# Keg_Cop_-_New_8-Pack.net
KiCad netlist of a schematic drawn in EAGLE
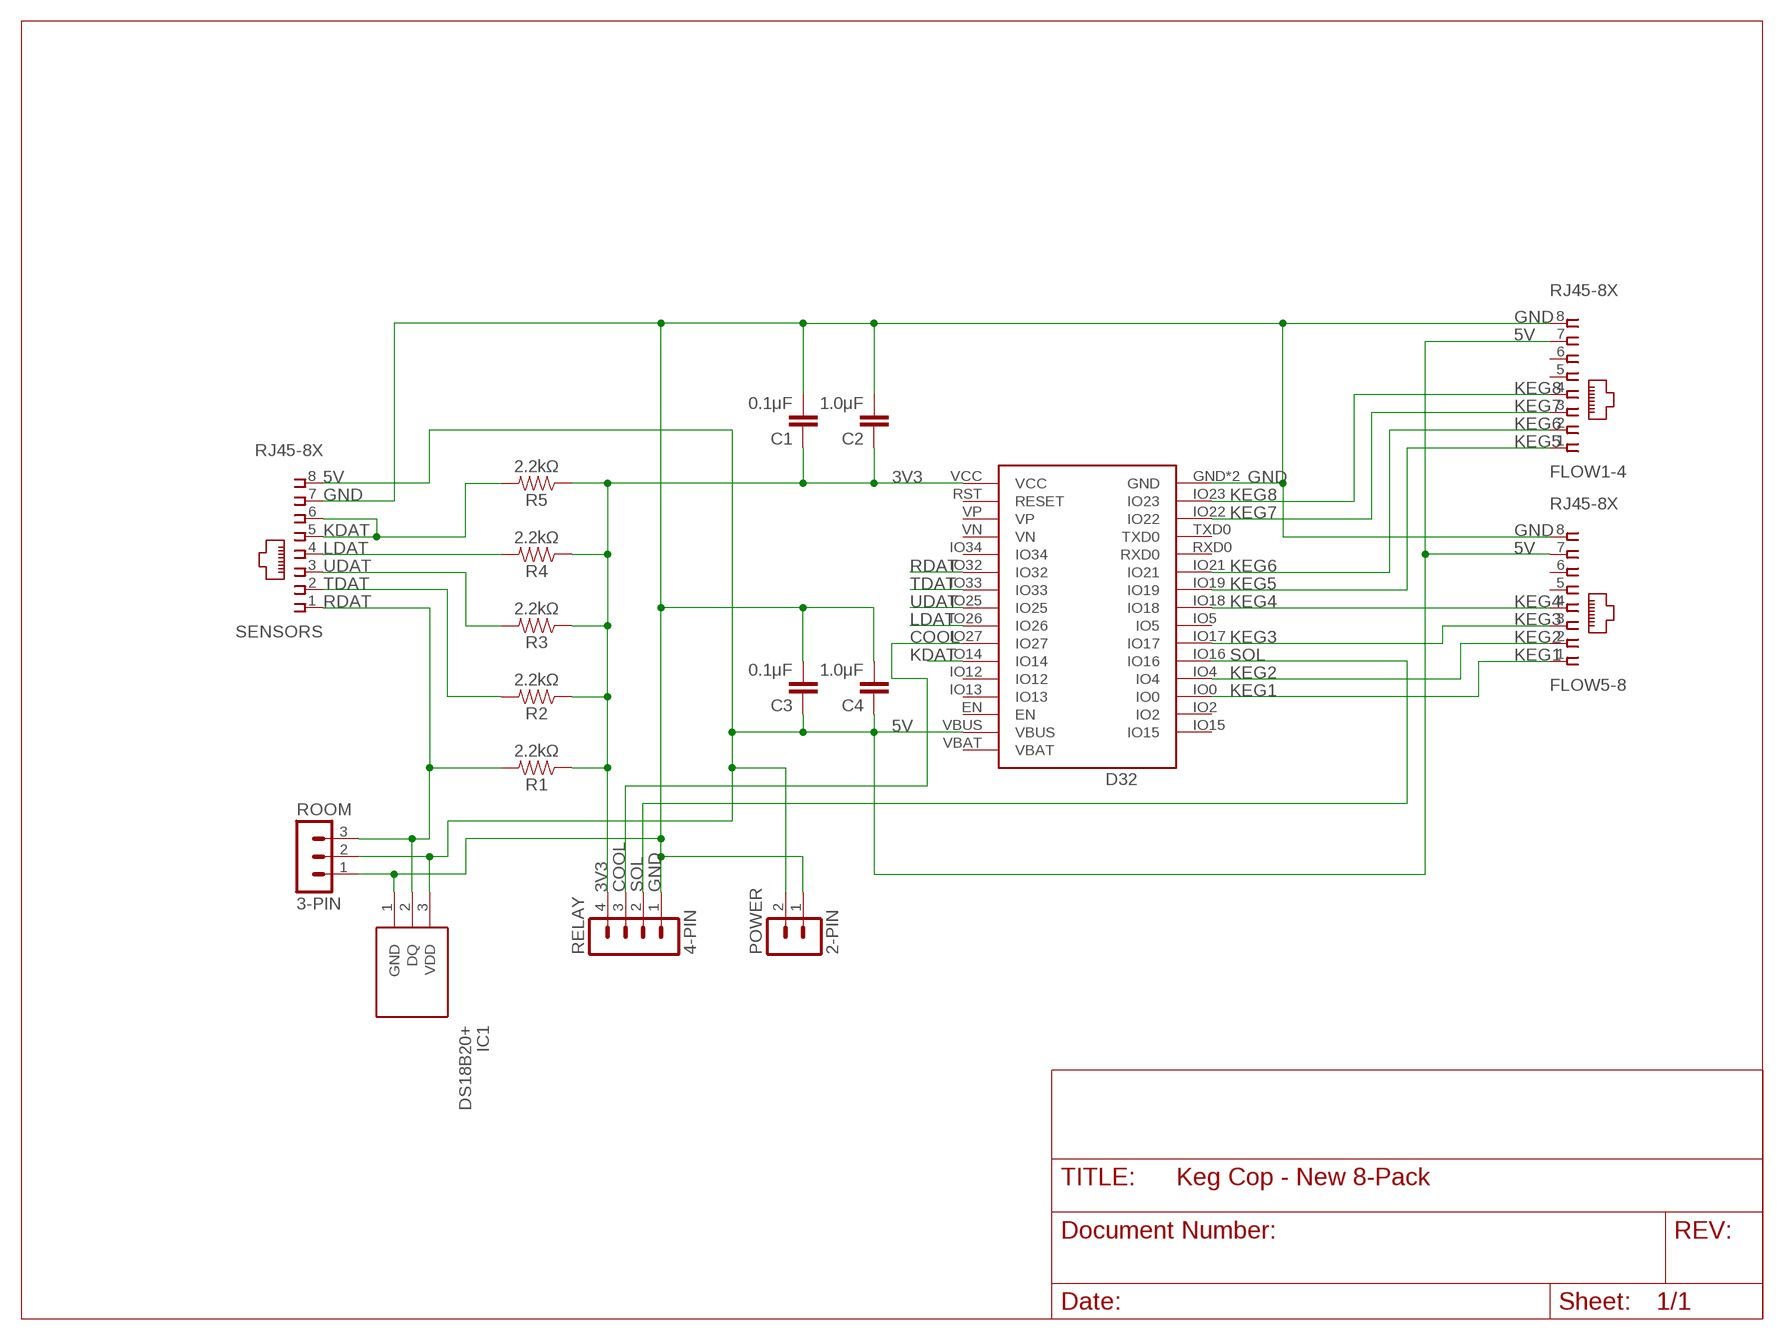
[diagram p0: schematic, sheet 1]

(export (version "E")
  (design (tool "Eeschema 10.0.6"))
  (components
    (comp (ref "C1")
      (value "0.1μF")
      (footprint "eagle-import:CAP_PTH-2.54")
      (libsource (lib "eagle-import") (part "CAP_CERAMIC_2.54"))
    )
    (comp (ref "C2")
      (value "1.0μF")
      (footprint "eagle-import:CAP_PTH-2.54")
      (libsource (lib "eagle-import") (part "CAP_CERAMIC_2.54"))
    )
    (comp (ref "C3")
      (value "0.1μF")
      (footprint "eagle-import:CAP_PTH-2.54")
      (libsource (lib "eagle-import") (part "CAP_CERAMIC_2.54"))
    )
    (comp (ref "C4")
      (value "1.0μF")
      (footprint "eagle-import:CAP_PTH-2.54")
      (libsource (lib "eagle-import") (part "CAP_CERAMIC_2.54"))
    )
    (comp (ref "D32")
      (value "Lolin D32")
      (footprint "eagle-import:D32_NO_BATT")
      (libsource (lib "eagle-import") (part "WEMOS-D32D32_NO_BATT"))
    )
    (comp (ref "FLOW1-4")
      (value "RJ45-8X")
      (footprint "eagle-import:RJ45-NO-SHIELD")
      (libsource (lib "eagle-import") (part "RJ45-8X"))
    )
    (comp (ref "FLOW5-8")
      (value "RJ45-8X")
      (footprint "eagle-import:RJ45-NO-SHIELD")
      (libsource (lib "eagle-import") (part "RJ45-8X"))
    )
    (comp (ref "IC1")
      (value "DS18B20+")
      (footprint "eagle-import:TO-92")
      (fields (field (name "MOUSER_PART_NUMBER") "700-DS18B20+"))
      (libsource (lib "eagle-import") (part "DS18B20+"))
    )
    (comp (ref "POWER")
      (value "2-PIN")
      (footprint "eagle-import:HDR-2_VERT")
      (libsource (lib "eagle-import") (part "HDR-2"))
    )
    (comp (ref "R1")
      (value "2.2kΩ")
      (footprint "eagle-import:AXIAL-0.3")
      (libsource (lib "eagle-import") (part "RESISTORAXIAL-0.3"))
    )
    (comp (ref "R2")
      (value "2.2kΩ")
      (footprint "eagle-import:AXIAL-0.3")
      (libsource (lib "eagle-import") (part "RESISTORAXIAL-0.3"))
    )
    (comp (ref "R3")
      (value "2.2kΩ")
      (footprint "eagle-import:AXIAL-0.3")
      (libsource (lib "eagle-import") (part "RESISTORAXIAL-0.3"))
    )
    (comp (ref "R4")
      (value "2.2kΩ")
      (footprint "eagle-import:AXIAL-0.3")
      (libsource (lib "eagle-import") (part "RESISTORAXIAL-0.3"))
    )
    (comp (ref "R5")
      (value "2.2kΩ")
      (footprint "eagle-import:AXIAL-0.3")
      (libsource (lib "eagle-import") (part "RESISTORAXIAL-0.3"))
    )
    (comp (ref "RELAY")
      (value "4-PIN")
      (footprint "eagle-import:MA04-1")
      (libsource (lib "eagle-import") (part "MA04-1"))
    )
    (comp (ref "ROOM")
      (value "3-PIN")
      (footprint "eagle-import:HDR-3_VERT")
      (libsource (lib "eagle-import") (part "HDR-3"))
    )
    (comp (ref "SENSORS")
      (value "RJ45-8X")
      (footprint "eagle-import:RJ45-NO-SHIELD")
      (libsource (lib "eagle-import") (part "RJ45-8X"))
    )
  )
  (nets
    (net (code "1") (name "/3V3") (class "Default")
      (node (ref "C1") (pin "1") (pinfunction "1_1") (pintype "passive"))
      (node (ref "C2") (pin "1") (pinfunction "1_1") (pintype "passive"))
      (node (ref "D32") (pin "VCC") (pinfunction "VCC_VCC") (pintype "power_in"))
      (node (ref "R1") (pin "P$1") (pinfunction "1_P$1") (pintype "passive"))
      (node (ref "R2") (pin "P$1") (pinfunction "1_P$1") (pintype "passive"))
      (node (ref "R3") (pin "P$1") (pinfunction "1_P$1") (pintype "passive"))
      (node (ref "R4") (pin "P$1") (pinfunction "1_P$1") (pintype "passive"))
      (node (ref "R5") (pin "P$1") (pinfunction "1_P$1") (pintype "passive"))
      (node (ref "RELAY") (pin "4") (pinfunction "4_4") (pintype "passive"))
    )
    (net (code "2") (name "/5V") (class "Default")
      (node (ref "C3") (pin "1") (pinfunction "1_1") (pintype "passive"))
      (node (ref "C4") (pin "1") (pinfunction "1_1") (pintype "passive"))
      (node (ref "D32") (pin "VBUS") (pinfunction "VBUS_VBUS") (pintype "bidirectional"))
      (node (ref "FLOW1-4") (pin "7") (pinfunction "7_7") (pintype "passive"))
      (node (ref "FLOW5-8") (pin "7") (pinfunction "7_7") (pintype "passive"))
      (node (ref "IC1") (pin "3") (pinfunction "VDD_3") (pintype "power_in"))
      (node (ref "POWER") (pin "2") (pinfunction "2_2") (pintype "passive"))
      (node (ref "ROOM") (pin "2") (pinfunction "2_2") (pintype "passive"))
      (node (ref "SENSORS") (pin "8") (pinfunction "8_8") (pintype "passive"))
    )
    (net (code "3") (name "/COOL") (class "Default")
      (node (ref "D32") (pin "IO27") (pinfunction "IO27_IO27") (pintype "bidirectional"))
      (node (ref "RELAY") (pin "3") (pinfunction "3_3") (pintype "passive"))
    )
    (net (code "4") (name "/GND") (class "Default")
      (node (ref "C1") (pin "2") (pinfunction "2_2") (pintype "passive"))
      (node (ref "C2") (pin "2") (pinfunction "2_2") (pintype "passive"))
      (node (ref "C3") (pin "2") (pinfunction "2_2") (pintype "passive"))
      (node (ref "C4") (pin "2") (pinfunction "2_2") (pintype "passive"))
      (node (ref "D32") (pin "GND") (pinfunction "GND_GND") (pintype "power_in"))
      (node (ref "D32") (pin "GND2") (pinfunction "GND_GND2") (pintype "power_in"))
      (node (ref "FLOW1-4") (pin "8") (pinfunction "8_8") (pintype "passive"))
      (node (ref "FLOW5-8") (pin "8") (pinfunction "8_8") (pintype "passive"))
      (node (ref "IC1") (pin "1") (pinfunction "GND_1") (pintype "power_in"))
      (node (ref "POWER") (pin "1") (pinfunction "1_1") (pintype "passive"))
      (node (ref "RELAY") (pin "1") (pinfunction "1_1") (pintype "passive"))
      (node (ref "ROOM") (pin "1") (pinfunction "1_1") (pintype "passive"))
      (node (ref "SENSORS") (pin "7") (pinfunction "7_7") (pintype "passive"))
    )
    (net (code "5") (name "/KDAT") (class "Default")
      (node (ref "D32") (pin "IO14") (pinfunction "IO14_IO14") (pintype "bidirectional"))
      (node (ref "R5") (pin "P$2") (pinfunction "2_P$2") (pintype "passive"))
      (node (ref "SENSORS") (pin "5") (pinfunction "5_5") (pintype "passive"))
      (node (ref "SENSORS") (pin "6") (pinfunction "6_6") (pintype "passive"))
    )
    (net (code "6") (name "/KEG1") (class "Default")
      (node (ref "D32") (pin "IO0") (pinfunction "IO0_IO0") (pintype "bidirectional"))
      (node (ref "FLOW5-8") (pin "1") (pinfunction "1_1") (pintype "passive"))
    )
    (net (code "7") (name "/KEG2") (class "Default")
      (node (ref "D32") (pin "IO4") (pinfunction "IO4_IO4") (pintype "bidirectional"))
      (node (ref "FLOW5-8") (pin "2") (pinfunction "2_2") (pintype "passive"))
    )
    (net (code "8") (name "/KEG3") (class "Default")
      (node (ref "D32") (pin "IO17") (pinfunction "IO17_IO17") (pintype "bidirectional"))
      (node (ref "FLOW5-8") (pin "3") (pinfunction "3_3") (pintype "passive"))
    )
    (net (code "9") (name "/KEG4") (class "Default")
      (node (ref "D32") (pin "IO18") (pinfunction "IO18_IO18") (pintype "bidirectional"))
      (node (ref "FLOW5-8") (pin "4") (pinfunction "4_4") (pintype "passive"))
    )
    (net (code "10") (name "/KEG5") (class "Default")
      (node (ref "D32") (pin "IO19") (pinfunction "IO19_IO19") (pintype "bidirectional"))
      (node (ref "FLOW1-4") (pin "1") (pinfunction "1_1") (pintype "passive"))
    )
    (net (code "11") (name "/KEG6") (class "Default")
      (node (ref "D32") (pin "IO21") (pinfunction "IO21_IO21") (pintype "bidirectional"))
      (node (ref "FLOW1-4") (pin "2") (pinfunction "2_2") (pintype "passive"))
    )
    (net (code "12") (name "/KEG7") (class "Default")
      (node (ref "D32") (pin "IO22") (pinfunction "IO22_IO22") (pintype "bidirectional"))
      (node (ref "FLOW1-4") (pin "3") (pinfunction "3_3") (pintype "passive"))
    )
    (net (code "13") (name "/KEG8") (class "Default")
      (node (ref "D32") (pin "IO23") (pinfunction "IO23_IO23") (pintype "bidirectional"))
      (node (ref "FLOW1-4") (pin "4") (pinfunction "4_4") (pintype "passive"))
    )
    (net (code "14") (name "/LDAT") (class "Default")
      (node (ref "D32") (pin "IO26") (pinfunction "IO26_IO26") (pintype "bidirectional"))
      (node (ref "R4") (pin "P$2") (pinfunction "2_P$2") (pintype "passive"))
      (node (ref "SENSORS") (pin "4") (pinfunction "4_4") (pintype "passive"))
    )
    (net (code "15") (name "/RDAT") (class "Default")
      (node (ref "D32") (pin "IO32") (pinfunction "IO32_IO32") (pintype "bidirectional"))
      (node (ref "IC1") (pin "2") (pinfunction "DQ_2") (pintype "bidirectional"))
      (node (ref "R1") (pin "P$2") (pinfunction "2_P$2") (pintype "passive"))
      (node (ref "ROOM") (pin "3") (pinfunction "3_3") (pintype "passive"))
      (node (ref "SENSORS") (pin "1") (pinfunction "1_1") (pintype "passive"))
    )
    (net (code "16") (name "/SOL") (class "Default")
      (node (ref "D32") (pin "IO16") (pinfunction "IO16_IO16") (pintype "bidirectional"))
      (node (ref "RELAY") (pin "2") (pinfunction "2_2") (pintype "passive"))
    )
    (net (code "17") (name "/TDAT") (class "Default")
      (node (ref "D32") (pin "IO33") (pinfunction "IO33_IO33") (pintype "bidirectional"))
      (node (ref "R2") (pin "P$2") (pinfunction "2_P$2") (pintype "passive"))
      (node (ref "SENSORS") (pin "2") (pinfunction "2_2") (pintype "passive"))
    )
    (net (code "18") (name "/UDAT") (class "Default")
      (node (ref "D32") (pin "IO25") (pinfunction "IO25_IO25") (pintype "bidirectional"))
      (node (ref "R3") (pin "P$2") (pinfunction "2_P$2") (pintype "passive"))
      (node (ref "SENSORS") (pin "3") (pinfunction "3_3") (pintype "passive"))
    )
    (net (code "19") (name "unconnected-(D32-PadEN)") (class "Default")
      (node (ref "D32") (pin "EN") (pinfunction "EN_EN") (pintype "bidirectional"))
    )
    (net (code "20") (name "unconnected-(D32-PadIO2)") (class "Default")
      (node (ref "D32") (pin "IO2") (pinfunction "IO2_IO2") (pintype "bidirectional"))
    )
    (net (code "21") (name "unconnected-(D32-PadIO5)") (class "Default")
      (node (ref "D32") (pin "IO5") (pinfunction "IO5_IO5") (pintype "bidirectional"))
    )
    (net (code "22") (name "unconnected-(D32-PadIO12)") (class "Default")
      (node (ref "D32") (pin "IO12") (pinfunction "IO12_IO12") (pintype "bidirectional"))
    )
    (net (code "23") (name "unconnected-(D32-PadIO13)") (class "Default")
      (node (ref "D32") (pin "IO13") (pinfunction "IO13_IO13") (pintype "bidirectional"))
    )
    (net (code "24") (name "unconnected-(D32-PadIO15)") (class "Default")
      (node (ref "D32") (pin "IO15") (pinfunction "IO15_IO15") (pintype "bidirectional"))
    )
    (net (code "25") (name "unconnected-(D32-PadIO34)") (class "Default")
      (node (ref "D32") (pin "IO34") (pinfunction "IO34_IO34") (pintype "bidirectional"))
    )
    (net (code "26") (name "unconnected-(D32-PadRXD0)") (class "Default")
      (node (ref "D32") (pin "RXD0") (pinfunction "RXD0_RXD0") (pintype "input"))
    )
    (net (code "27") (name "unconnected-(D32-PadTXD0)") (class "Default")
      (node (ref "D32") (pin "TXD0") (pinfunction "TXD0_TXD0") (pintype "output"))
    )
    (net (code "28") (name "unconnected-(D32-PadVBAT)") (class "Default")
      (node (ref "D32") (pin "VBAT") (pinfunction "VBAT_VBAT") (pintype "bidirectional"))
    )
    (net (code "29") (name "unconnected-(D32-PadVN)") (class "Default")
      (node (ref "D32") (pin "VN") (pinfunction "VN_VN") (pintype "bidirectional"))
    )
    (net (code "30") (name "unconnected-(D32-PadVP)") (class "Default")
      (node (ref "D32") (pin "VP") (pinfunction "VP_VP") (pintype "bidirectional"))
    )
    (net (code "31") (name "unconnected-(D32-RESET-PadRST)") (class "Default")
      (node (ref "D32") (pin "RST") (pinfunction "RESET_RST") (pintype "bidirectional"))
    )
    (net (code "32") (name "unconnected-(FLOW1-4-Pad5)") (class "Default")
      (node (ref "FLOW1-4") (pin "5") (pinfunction "5_5") (pintype "passive"))
    )
    (net (code "33") (name "unconnected-(FLOW1-4-Pad6)") (class "Default")
      (node (ref "FLOW1-4") (pin "6") (pinfunction "6_6") (pintype "passive"))
    )
    (net (code "34") (name "unconnected-(FLOW5-8-Pad5)") (class "Default")
      (node (ref "FLOW5-8") (pin "5") (pinfunction "5_5") (pintype "passive"))
    )
    (net (code "35") (name "unconnected-(FLOW5-8-Pad6)") (class "Default")
      (node (ref "FLOW5-8") (pin "6") (pinfunction "6_6") (pintype "passive"))
    )
  )
)
